# POWER.net
KiCad netlist of a schematic drawn in Altium Designer
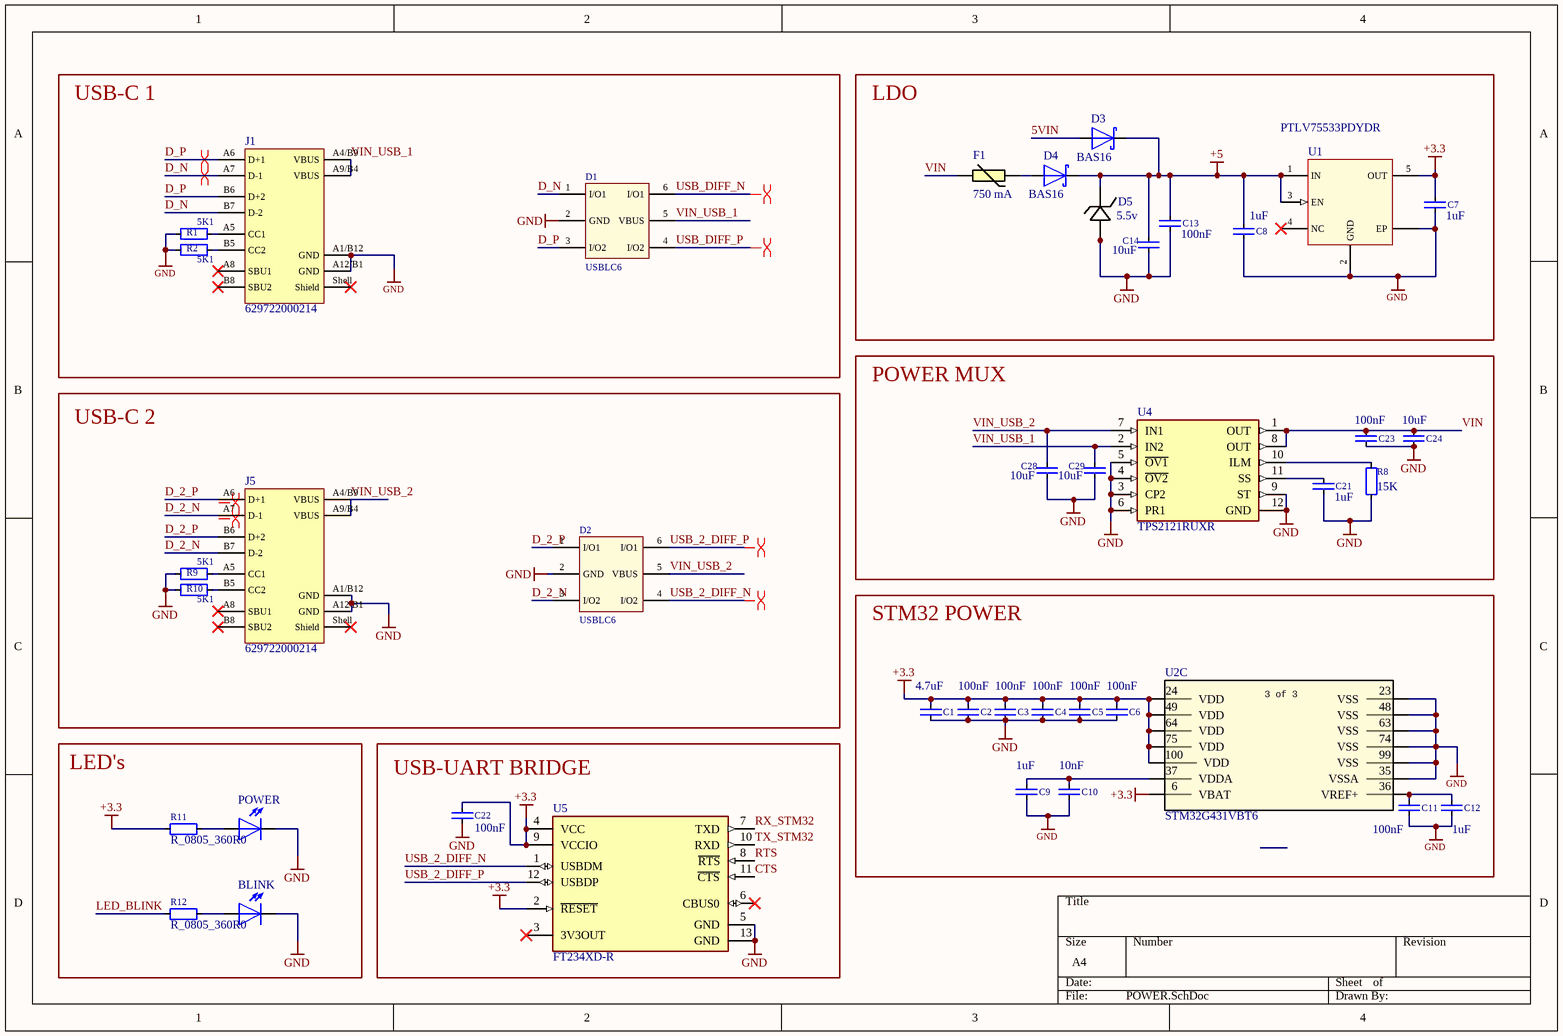
[diagram p0: POWER.SchDoc]

(export (version "E")
  (design (tool "Eeschema 10.0.6"))
  (components
    (comp (ref "BLINK")
      (value "LED_1206_GREEN")
      (footprint "WL-SMRW_1205_normal use")
      (description "LED, SMD, 1206, green")
      (fields
        (field (name "MANUFACTURER") "Würth Elektronik")
        (field (name "MANUFACTURER PART NUMBER") "156120GS75000")
      )
      (libsource (lib "CPNE-TI Electronic") (part "LED"))
    )
    (comp (ref "C1")
      (value "C_1206_4u70_X7R_25V")
      (footprint "SMD_1026_footprint")
      (fields
        (field (name "MANUFACTURER PART NUMBER") "12063C475KAT4A")
        (field (name "MANUFACTURER") "AVX Kyocera")
        (field (name "DISPLAYED VALUE") "4.7uF")
      )
      (libsource (lib "CPNE-TI Electronic") (part "Capacitor_Non-Polarized"))
    )
    (comp (ref "C2")
      (value "C_0805_100n0_X7R")
      (footprint "SMD_0805_footprint")
      (fields
        (field (name "MANUFACTURER PART NUMBER") "885012207098")
        (field (name "MANUFACTURER") "Würth Elektronik")
        (field (name "DISPLAYED VALUE") "100nF")
      )
      (libsource (lib "CPNE-TI Electronic") (part "Capacitor_Non-Polarized"))
    )
    (comp (ref "C3")
      (value "C_0805_100n0_X7R")
      (footprint "SMD_0805_footprint")
      (fields
        (field (name "MANUFACTURER PART NUMBER") "885012207098")
        (field (name "MANUFACTURER") "Würth Elektronik")
        (field (name "DISPLAYED VALUE") "100nF")
      )
      (libsource (lib "CPNE-TI Electronic") (part "Capacitor_Non-Polarized"))
    )
    (comp (ref "C4")
      (value "C_0805_100n0_X7R")
      (footprint "SMD_0805_footprint")
      (fields
        (field (name "MANUFACTURER PART NUMBER") "885012207098")
        (field (name "MANUFACTURER") "Würth Elektronik")
        (field (name "DISPLAYED VALUE") "100nF")
      )
      (libsource (lib "CPNE-TI Electronic") (part "Capacitor_Non-Polarized"))
    )
    (comp (ref "C5")
      (value "C_0805_100n0_X7R")
      (footprint "SMD_0805_footprint")
      (fields
        (field (name "MANUFACTURER PART NUMBER") "885012207098")
        (field (name "MANUFACTURER") "Würth Elektronik")
        (field (name "DISPLAYED VALUE") "100nF")
      )
      (libsource (lib "CPNE-TI Electronic") (part "Capacitor_Non-Polarized"))
    )
    (comp (ref "C6")
      (value "C_0805_100n0_X7R")
      (footprint "SMD_0805_footprint")
      (fields
        (field (name "MANUFACTURER PART NUMBER") "885012207098")
        (field (name "MANUFACTURER") "Würth Elektronik")
        (field (name "DISPLAYED VALUE") "100nF")
      )
      (libsource (lib "CPNE-TI Electronic") (part "Capacitor_Non-Polarized"))
    )
    (comp (ref "C7")
      (value "C_0805_1u00_X7R_16V")
      (footprint "SMD_0805_footprint")
      (description "Ceramic Capacitor 1uF 16V 10% X7R SMD 0805")
      (fields
        (field (name "MANUFACTURER") "multicomp Pro")
        (field (name "DISPLAYED VALUE") "1uF")
        (field (name "MANUFACTURER PART NUMBER") "MC0805B105K160CT")
      )
      (libsource (lib "CPNE-TI Electronic") (part "Capacitor_Non-Polarized"))
    )
    (comp (ref "C8")
      (value "C_0805_1u00_X7R_16V")
      (footprint "SMD_0805_footprint")
      (description "Ceramic Capacitor 1uF 16V 10% X7R SMD 0805")
      (fields
        (field (name "MANUFACTURER") "multicomp Pro")
        (field (name "DISPLAYED VALUE") "1uF")
        (field (name "MANUFACTURER PART NUMBER") "MC0805B105K160CT")
      )
      (libsource (lib "CPNE-TI Electronic") (part "Capacitor_Non-Polarized"))
    )
    (comp (ref "C9")
      (value "C_0805_1u00_X7R_16V")
      (footprint "SMD_0805_footprint")
      (description "Ceramic Capacitor 1uF 16V 10% X7R SMD 0805")
      (fields
        (field (name "MANUFACTURER") "multicomp Pro")
        (field (name "DISPLAYED VALUE") "1uF")
        (field (name "MANUFACTURER PART NUMBER") "MC0805B105K160CT")
      )
      (libsource (lib "CPNE-TI Electronic") (part "Capacitor_Non-Polarized"))
    )
    (comp (ref "C10")
      (value "C_0805_10n00_X7R_50V")
      (footprint "SMD_0805_footprint")
      (description "Multilayer Ceramic Capacitor 0.01uF 0805")
      (fields
        (field (name "MANUFACTURER") "Würth Elektronik")
        (field (name "DISPLAYED VALUE") "10nF")
        (field (name "MANUFACTURER PART NUMBER") "8850 1220 7092")
      )
      (libsource (lib "CPNE-TI Electronic") (part "Capacitor_Non-Polarized"))
    )
    (comp (ref "C11")
      (value "C_0805_100n0_X7R")
      (footprint "SMD_0805_footprint")
      (fields
        (field (name "MANUFACTURER PART NUMBER") "885012207098")
        (field (name "MANUFACTURER") "Würth Elektronik")
        (field (name "DISPLAYED VALUE") "100nF")
      )
      (libsource (lib "CPNE-TI Electronic") (part "Capacitor_Non-Polarized"))
    )
    (comp (ref "C12")
      (value "C_0805_1u00_X7R_16V")
      (footprint "SMD_0805_footprint")
      (description "Ceramic Capacitor 1uF 16V 10% X7R SMD 0805")
      (fields
        (field (name "MANUFACTURER") "multicomp Pro")
        (field (name "DISPLAYED VALUE") "1uF")
        (field (name "MANUFACTURER PART NUMBER") "MC0805B105K160CT")
      )
      (libsource (lib "CPNE-TI Electronic") (part "Capacitor_Non-Polarized"))
    )
    (comp (ref "C13")
      (value "C_0805_100n0_X7R")
      (footprint "SMD_0805_footprint")
      (fields
        (field (name "MANUFACTURER PART NUMBER") "885012207098")
        (field (name "MANUFACTURER") "Würth Elektronik")
        (field (name "DISPLAYED VALUE") "100nF")
      )
      (libsource (lib "CPNE-TI Electronic") (part "Capacitor_Non-Polarized"))
    )
    (comp (ref "C14")
      (value "C_1206_10u0_X7R_25V")
      (footprint "SMD_1026_footprint")
      (description "10μF ±10% 25V Ceramic Capacitor X7R 1206 (3216 Metric)")
      (fields
        (field (name "MANUFACTURER PART NUMBER") "885012208069")
        (field (name "DISPLAYED VALUE") "10uF")
        (field (name "MANUFACTURER") "Würth Elektronik")
      )
      (libsource (lib "CPNE-TI Electronic") (part "Capacitor_Non-Polarized"))
    )
    (comp (ref "C21")
      (value "C_0805_1u00_X7R_16V")
      (footprint "SMD_0805_footprint")
      (description "Ceramic Capacitor 1uF 16V 10% X7R SMD 0805")
      (fields
        (field (name "MANUFACTURER") "multicomp Pro")
        (field (name "DISPLAYED VALUE") "1uF")
        (field (name "MANUFACTURER PART NUMBER") "MC0805B105K160CT")
      )
      (libsource (lib "CPNE-TI Electronic") (part "Capacitor_Non-Polarized"))
    )
    (comp (ref "C22")
      (value "C_0805_100n0_X7R")
      (footprint "SMD_0805_footprint")
      (fields
        (field (name "MANUFACTURER PART NUMBER") "885012207098")
        (field (name "MANUFACTURER") "Würth Elektronik")
        (field (name "DISPLAYED VALUE") "100nF")
      )
      (libsource (lib "CPNE-TI Electronic") (part "Capacitor_Non-Polarized"))
    )
    (comp (ref "C23")
      (value "C_0805_100n0_X7R")
      (footprint "SMD_0805_footprint")
      (fields
        (field (name "MANUFACTURER PART NUMBER") "885012207098")
        (field (name "MANUFACTURER") "Würth Elektronik")
        (field (name "DISPLAYED VALUE") "100nF")
      )
      (libsource (lib "CPNE-TI Electronic") (part "Capacitor_Non-Polarized"))
    )
    (comp (ref "C24")
      (value "C_1206_10u0_X7R_25V")
      (footprint "SMD_1026_footprint")
      (description "10μF ±10% 25V Ceramic Capacitor X7R 1206 (3216 Metric)")
      (fields
        (field (name "MANUFACTURER PART NUMBER") "885012208069")
        (field (name "DISPLAYED VALUE") "10uF")
        (field (name "MANUFACTURER") "Würth Elektronik")
      )
      (libsource (lib "CPNE-TI Electronic") (part "Capacitor_Non-Polarized"))
    )
    (comp (ref "C28")
      (value "C_1206_10u0_X7R_25V")
      (footprint "SMD_1026_footprint")
      (description "10μF ±10% 25V Ceramic Capacitor X7R 1206 (3216 Metric)")
      (fields
        (field (name "MANUFACTURER PART NUMBER") "885012208069")
        (field (name "DISPLAYED VALUE") "10uF")
        (field (name "MANUFACTURER") "Würth Elektronik")
      )
      (libsource (lib "CPNE-TI Electronic") (part "Capacitor_Non-Polarized"))
    )
    (comp (ref "C29")
      (value "C_1206_10u0_X7R_25V")
      (footprint "SMD_1026_footprint")
      (description "10μF ±10% 25V Ceramic Capacitor X7R 1206 (3216 Metric)")
      (fields
        (field (name "MANUFACTURER PART NUMBER") "885012208069")
        (field (name "DISPLAYED VALUE") "10uF")
        (field (name "MANUFACTURER") "Würth Elektronik")
      )
      (libsource (lib "CPNE-TI Electronic") (part "Capacitor_Non-Polarized"))
    )
    (comp (ref "D1")
      (value "USBLC6-2SC6")
      (footprint "SOT23-6L_V")
      (description "5A 17V 6V Unidirectional 5.25V SOT-23-6L ESD and Surge Protection (TVS/ESD) ROHS")
      (fields (field (name "DISPLAYED VALUE") "USBLC6") (field (name "MANUFACTURER") "ST Microelectronics"))
      (libsource (lib "CPNE-TI Electronic") (part "USBLC6-2SC6-Symbol-1"))
    )
    (comp (ref "D2")
      (value "USBLC6-2SC6")
      (footprint "SOT23-6L_V")
      (description "5A 17V 6V Unidirectional 5.25V SOT-23-6L ESD and Surge Protection (TVS/ESD) ROHS")
      (fields (field (name "DISPLAYED VALUE") "USBLC6") (field (name "MANUFACTURER") "ST Microelectronics"))
      (libsource (lib "CPNE-TI Electronic") (part "USBLC6-2SC6-Symbol-1"))
    )
    (comp (ref "D3")
      (value "BAS16LT3G")
      (footprint "ONSC-SOT-23-3-318-08_V")
      (description "Rectifier Diode Small Signal Switching 0.2A 6ns 3-Pin SOT-23 T/R")
      (fields (field (name "DISPLAYED VALUE") "BAS16") (field (name "MANUFACTURER") "Onsemi"))
      (libsource (lib "CPNE-TI Electronic") (part "Schottky Diode SOT-23"))
    )
    (comp (ref "D4")
      (value "BAS16LT3G")
      (footprint "ONSC-SOT-23-3-318-08_V")
      (description "Rectifier Diode Small Signal Switching 0.2A 6ns 3-Pin SOT-23 T/R")
      (fields (field (name "DISPLAYED VALUE") "BAS16") (field (name "MANUFACTURER") "Onsemi"))
      (libsource (lib "CPNE-TI Electronic") (part "Schottky Diode SOT-23"))
    )
    (comp (ref "D5")
      (value "D5V0H1U2LP1610-7")
      (footprint "D5V0H1U2LP1610-7")
      (description "TVS Diode")
      (fields (field (name "DISPLAYED VALUE") "5.5v") (field (name "MANUFACTURER") "Diodes Incorporated"))
      (libsource (lib "CPNE-TI Electronic") (part "D5V0H1U2LP1610-7"))
    )
    (comp (ref "F1")
      (value "0ZCG0075FF2C")
      (footprint "0ZCG0075FF2C")
      (description "Polymérique PTC Resettable Fuse 16V 750 mA Ih Montage en surface 1812")
      (fields (field (name "MANUFACTURER") "Bel Fuse Inc.") (field (name "DISPLAYED VALUE") "750 mA"))
      (libsource (lib "CPNE-TI Electronic") (part "0ZCG0075FF2C"))
    )
    (comp (ref "J1")
      (value "629722000214")
      (footprint "629722000214")
      (description "Usb Conn, R/a, Type C 2.0, Rcpt, 16POS Rohs Compliant: Yes")
      (fields (field (name "MANUFACTURER") "Würth Elektronik"))
      (libsource (lib "CPNE-TI Electronic") (part "USB 2.0_Type C_Receptacle_1 Port_629722000214"))
    )
    (comp (ref "J5")
      (value "629722000214")
      (footprint "629722000214")
      (description "Usb Conn, R/a, Type C 2.0, Rcpt, 16POS Rohs Compliant: Yes")
      (fields (field (name "MANUFACTURER") "Würth Elektronik"))
      (libsource (lib "CPNE-TI Electronic") (part "USB 2.0_Type C_Receptacle_1 Port_629722000214"))
    )
    (comp (ref "POWER")
      (value "LED_1206_GREEN")
      (footprint "WL-SMRW_1205_normal use")
      (description "LED, SMD, 1206, green")
      (fields
        (field (name "MANUFACTURER") "Würth Elektronik")
        (field (name "MANUFACTURER PART NUMBER") "156120GS75000")
      )
      (libsource (lib "CPNE-TI Electronic") (part "LED"))
    )
    (comp (ref "R1")
      (value "R_0805_5K10")
      (footprint "SMD_0805_footprint")
      (description "Res Thick Film 0805 5.1K Ohm 1% 1/8W ±100ppm/°C Molded SMD Punched Carrier T/R")
      (fields
        (field (name "DISPLAYED VALUE") "5K1")
        (field (name "MANUFACTURER PART NUMBER") "ERJ-6ENF5101V")
        (field (name "MANUFACTURER") "Panasonic")
      )
      (libsource (lib "CPNE-TI Electronic") (part "Resistor_Symbol"))
    )
    (comp (ref "R2")
      (value "R_0805_5K10")
      (footprint "SMD_0805_footprint")
      (description "Res Thick Film 0805 5.1K Ohm 1% 1/8W ±100ppm/°C Molded SMD Punched Carrier T/R")
      (fields
        (field (name "DISPLAYED VALUE") "5K1")
        (field (name "MANUFACTURER PART NUMBER") "ERJ-6ENF5101V")
        (field (name "MANUFACTURER") "Panasonic")
      )
      (libsource (lib "CPNE-TI Electronic") (part "Resistor_Symbol"))
    )
    (comp (ref "R8")
      (value "R_0805_15K_0.125W")
      (footprint "SMD_0805_footprint")
      (description "Res Thick Film 0805 1.5K Ohm 1% 0.125W(1/8W) +/-100ppm/C Molded SMD Automotive Punched T/R")
      (fields
        (field (name "MANUFACTURER PART NUMBER") "ERJ-6ENF1501V")
        (field (name "DISPLAYED VALUE") "15K")
        (field (name "MANUFACTURER") "Panasonic")
      )
      (libsource (lib "") (part "Resistor_Symbol_1"))
    )
    (comp (ref "R9")
      (value "R_0805_5K10")
      (footprint "SMD_0805_footprint")
      (description "Res Thick Film 0805 5.1K Ohm 1% 1/8W ±100ppm/°C Molded SMD Punched Carrier T/R")
      (fields
        (field (name "DISPLAYED VALUE") "5K1")
        (field (name "MANUFACTURER PART NUMBER") "ERJ-6ENF5101V")
        (field (name "MANUFACTURER") "Panasonic")
      )
      (libsource (lib "CPNE-TI Electronic") (part "Resistor_Symbol"))
    )
    (comp (ref "R10")
      (value "R_0805_5K10")
      (footprint "SMD_0805_footprint")
      (description "Res Thick Film 0805 5.1K Ohm 1% 1/8W ±100ppm/°C Molded SMD Punched Carrier T/R")
      (fields
        (field (name "DISPLAYED VALUE") "5K1")
        (field (name "MANUFACTURER PART NUMBER") "ERJ-6ENF5101V")
        (field (name "MANUFACTURER") "Panasonic")
      )
      (libsource (lib "CPNE-TI Electronic") (part "Resistor_Symbol"))
    )
    (comp (ref "R11")
      (value "R_0805_360R0")
      (footprint "SMD_0805_footprint")
      (description "Res Thick Film 0805 360 Ohm 1% 0.125W ±100ppm/°C Molded SMD Punched Carrier T/R")
      (fields
        (field (name "MANUFACTURER PART NUMBER") "ERJ-6ENF3600V")
        (field (name "MANUFACTURER") "Panasonic")
      )
      (libsource (lib "CPNE-TI Electronic") (part "Resistor_Symbol"))
    )
    (comp (ref "R12")
      (value "R_0805_360R0")
      (footprint "SMD_0805_footprint")
      (description "Res Thick Film 0805 360 Ohm 1% 0.125W ±100ppm/°C Molded SMD Punched Carrier T/R")
      (fields
        (field (name "MANUFACTURER PART NUMBER") "ERJ-6ENF3600V")
        (field (name "MANUFACTURER") "Panasonic")
      )
      (libsource (lib "CPNE-TI Electronic") (part "Resistor_Symbol"))
    )
    (comp (ref "U1")
      (value "PTLV75533PDYDR")
      (footprint "DYD0005A-MFG")
      (description "500-mA high-PSRR low-IQ low-dropout voltage regulator with enable 5-SOT-23 -40 to 125")
      (fields (field (name "MANUFACTURER") "Texas Instruments"))
      (libsource (lib "CPNE-TI Electronic") (part "PTLV75533PDYDR"))
    )
    (comp (ref "U2")
      (value "STM32G431VBT6")
      (footprint "LQFP100")
      (description "Microcontroller 32-Bit ARM Cortex-M4 RISC 128KB Flash 1.71V to 3.6V 100-Pin LQFP")
      (libsource (lib "CPNE-TI Electronic") (part "STM32G431VBT6"))
    )
    (comp (ref "U4")
      (value "TPS2121RUXR")
      (footprint "FP-RUX0012A-MFG")
      (description "2.7-V to 22-V, 56-mΩ, 4.5-A, power mux with seamless switchover 12-VQFN-HR -40 to 125")
      (libsource (lib "CPNE-TI Electronic") (part "7e2eec2e55e3eba557c36dfb5d176d9"))
    )
    (comp (ref "U5")
      (value "FT234XD-R")
      (footprint "FP-DFN-12-MFG")
      (description "Tape & Reel (TR) 2006 UART USB 2.0 interface controller 2.97V~5.5V 800mum 8mA 3Mbps")
      (libsource (lib "CPNE-TI Electronic") (part "4bef3367ed9f9051bcb84ab46edda1c"))
    )
  )
  (nets
    (net (code "1") (name "+3.3") (class "Default")
      (node (ref "C1") (pin "2") (pinfunction "2_2") (pintype "passive"))
      (node (ref "C2") (pin "2") (pinfunction "2_2") (pintype "passive"))
      (node (ref "C22") (pin "1") (pinfunction "1_1") (pintype "passive"))
      (node (ref "C3") (pin "2") (pinfunction "2_2") (pintype "passive"))
      (node (ref "C4") (pin "2") (pinfunction "2_2") (pintype "passive"))
      (node (ref "C5") (pin "2") (pinfunction "2_2") (pintype "passive"))
      (node (ref "C6") (pin "2") (pinfunction "2_2") (pintype "passive"))
      (node (ref "C7") (pin "2") (pinfunction "2_2") (pintype "passive"))
      (node (ref "R11") (pin "1") (pinfunction "1_1") (pintype "passive"))
      (node (ref "U1") (pin "5") (pinfunction "OUT_5") (pintype "passive"))
      (node (ref "U2") (pin "100") (pinfunction "VDD_100") (pintype "power_in"))
      (node (ref "U2") (pin "24") (pinfunction "VDD_24") (pintype "power_in"))
      (node (ref "U2") (pin "49") (pinfunction "VDD_49") (pintype "power_in"))
      (node (ref "U2") (pin "6") (pinfunction "VBAT_6") (pintype "power_in"))
      (node (ref "U2") (pin "64") (pinfunction "VDD_64") (pintype "power_in"))
      (node (ref "U2") (pin "75") (pinfunction "VDD_75") (pintype "power_in"))
      (node (ref "U5") (pin "2") (pinfunction "~{RESET}_2") (pintype "input"))
      (node (ref "U5") (pin "4") (pinfunction "VCC_4") (pintype "power_in"))
      (node (ref "U5") (pin "9") (pinfunction "VCCIO_9") (pintype "power_in"))
    )
    (net (code "2") (name "+5") (class "Default")
      (node (ref "C13") (pin "2") (pinfunction "2_2") (pintype "passive"))
      (node (ref "C14") (pin "2") (pinfunction "2_2") (pintype "passive"))
      (node (ref "C8") (pin "2") (pinfunction "2_2") (pintype "passive"))
      (node (ref "D3") (pin "3") (pinfunction "K_3") (pintype "passive"))
      (node (ref "D4") (pin "3") (pinfunction "K_3") (pintype "passive"))
      (node (ref "D5") (pin "1") (pinfunction "1_1") (pintype "passive"))
      (node (ref "U1") (pin "1") (pinfunction "IN_1") (pintype "power_in"))
      (node (ref "U1") (pin "3") (pinfunction "EN_3") (pintype "input"))
    )
    (net (code "3") (name "/5VIN") (class "Default")
      (node (ref "D3") (pin "1") (pinfunction "A_1") (pintype "passive"))
    )
    (net (code "4") (name "/CTS") (class "Default")
      (node (ref "U5") (pin "11") (pinfunction "~{CTS}_11") (pintype "input"))
    )
    (net (code "5") (name "/D_2_N") (class "Default")
      (node (ref "D2") (pin "3") (pinfunction "I/O2_3") (pintype "passive"))
      (node (ref "J5") (pin "A7") (pinfunction "D-1_A7") (pintype "passive"))
      (node (ref "J5") (pin "B7") (pinfunction "D-2_B7") (pintype "passive"))
    )
    (net (code "6") (name "/D_2_P") (class "Default")
      (node (ref "D2") (pin "1") (pinfunction "I/O1_1") (pintype "passive"))
      (node (ref "J5") (pin "A6") (pinfunction "D+1_A6") (pintype "passive"))
      (node (ref "J5") (pin "B6") (pinfunction "D+2_B6") (pintype "passive"))
    )
    (net (code "7") (name "/D_N") (class "Default")
      (node (ref "D1") (pin "1") (pinfunction "I/O1_1") (pintype "passive"))
      (node (ref "J1") (pin "A7") (pinfunction "D-1_A7") (pintype "passive"))
      (node (ref "J1") (pin "B7") (pinfunction "D-2_B7") (pintype "passive"))
    )
    (net (code "8") (name "/D_P") (class "Default")
      (node (ref "D1") (pin "3") (pinfunction "I/O2_3") (pintype "passive"))
      (node (ref "J1") (pin "A6") (pinfunction "D+1_A6") (pintype "passive"))
      (node (ref "J1") (pin "B6") (pinfunction "D+2_B6") (pintype "passive"))
    )
    (net (code "9") (name "/LED_BLINK") (class "Default")
      (node (ref "R12") (pin "1") (pinfunction "1_1") (pintype "passive"))
    )
    (net (code "10") (name "/RTS") (class "Default")
      (node (ref "U5") (pin "8") (pinfunction "~{RTS}_8") (pintype "input"))
    )
    (net (code "11") (name "/RX_STM32") (class "Default")
      (node (ref "U5") (pin "7") (pinfunction "TXD_7") (pintype "output"))
    )
    (net (code "12") (name "/TX_STM32") (class "Default")
      (node (ref "U5") (pin "10") (pinfunction "RXD_10") (pintype "output"))
    )
    (net (code "13") (name "/USB_2_DIFF_N") (class "Default")
      (node (ref "D2") (pin "4") (pinfunction "I/O2_4") (pintype "passive"))
      (node (ref "U5") (pin "1") (pinfunction "USBDM_1") (pintype "bidirectional"))
    )
    (net (code "14") (name "/USB_2_DIFF_P") (class "Default")
      (node (ref "D2") (pin "6") (pinfunction "I/O1_6") (pintype "passive"))
      (node (ref "U5") (pin "12") (pinfunction "USBDP_12") (pintype "bidirectional"))
    )
    (net (code "15") (name "/USB_DIFF_N") (class "Default")
      (node (ref "D1") (pin "6") (pinfunction "I/O1_6") (pintype "passive"))
    )
    (net (code "16") (name "/USB_DIFF_P") (class "Default")
      (node (ref "D1") (pin "4") (pinfunction "I/O2_4") (pintype "passive"))
    )
    (net (code "17") (name "/VIN") (class "Default")
      (node (ref "C23") (pin "2") (pinfunction "2_2") (pintype "passive"))
      (node (ref "C24") (pin "2") (pinfunction "2_2") (pintype "passive"))
      (node (ref "F1") (pin "2") (pinfunction "2_2") (pintype "passive"))
      (node (ref "U4") (pin "1") (pinfunction "OUT_1") (pintype "output"))
      (node (ref "U4") (pin "8") (pinfunction "OUT_8") (pintype "output"))
    )
    (net (code "18") (name "/VIN_USB_1") (class "Default")
      (node (ref "C29") (pin "2") (pinfunction "2_2") (pintype "passive"))
      (node (ref "D1") (pin "5") (pinfunction "VBUS_5") (pintype "power_in"))
      (node (ref "J1") (pin "A4/B9") (pinfunction "VBUS_A4/B9") (pintype "passive"))
      (node (ref "J1") (pin "A9/B4") (pinfunction "VBUS_A9/B4") (pintype "passive"))
      (node (ref "U4") (pin "2") (pinfunction "IN2_2") (pintype "input"))
    )
    (net (code "19") (name "/VIN_USB_2") (class "Default")
      (node (ref "C28") (pin "2") (pinfunction "2_2") (pintype "passive"))
      (node (ref "D2") (pin "5") (pinfunction "VBUS_5") (pintype "power_in"))
      (node (ref "J5") (pin "A4/B9") (pinfunction "VBUS_A4/B9") (pintype "passive"))
      (node (ref "J5") (pin "A9/B4") (pinfunction "VBUS_A9/B4") (pintype "passive"))
      (node (ref "U4") (pin "7") (pinfunction "IN1_7") (pintype "input"))
    )
    (net (code "20") (name "GND") (class "Default")
      (node (ref "BLINK") (pin "1") (pinfunction "K_1") (pintype "passive"))
      (node (ref "C1") (pin "1") (pinfunction "1_1") (pintype "passive"))
      (node (ref "C10") (pin "1") (pinfunction "1_1") (pintype "passive"))
      (node (ref "C11") (pin "1") (pinfunction "1_1") (pintype "passive"))
      (node (ref "C12") (pin "1") (pinfunction "1_1") (pintype "passive"))
      (node (ref "C13") (pin "1") (pinfunction "1_1") (pintype "passive"))
      (node (ref "C14") (pin "1") (pinfunction "1_1") (pintype "passive"))
      (node (ref "C2") (pin "1") (pinfunction "1_1") (pintype "passive"))
      (node (ref "C21") (pin "1") (pinfunction "1_1") (pintype "passive"))
      (node (ref "C22") (pin "2") (pinfunction "2_2") (pintype "passive"))
      (node (ref "C23") (pin "1") (pinfunction "1_1") (pintype "passive"))
      (node (ref "C24") (pin "1") (pinfunction "1_1") (pintype "passive"))
      (node (ref "C28") (pin "1") (pinfunction "1_1") (pintype "passive"))
      (node (ref "C29") (pin "1") (pinfunction "1_1") (pintype "passive"))
      (node (ref "C3") (pin "1") (pinfunction "1_1") (pintype "passive"))
      (node (ref "C4") (pin "1") (pinfunction "1_1") (pintype "passive"))
      (node (ref "C5") (pin "1") (pinfunction "1_1") (pintype "passive"))
      (node (ref "C6") (pin "1") (pinfunction "1_1") (pintype "passive"))
      (node (ref "C7") (pin "1") (pinfunction "1_1") (pintype "passive"))
      (node (ref "C8") (pin "1") (pinfunction "1_1") (pintype "passive"))
      (node (ref "C9") (pin "1") (pinfunction "1_1") (pintype "passive"))
      (node (ref "D1") (pin "2") (pinfunction "GND_2") (pintype "power_in"))
      (node (ref "D2") (pin "2") (pinfunction "GND_2") (pintype "power_in"))
      (node (ref "D5") (pin "2") (pinfunction "2_2") (pintype "passive"))
      (node (ref "J1") (pin "A1/B12") (pinfunction "GND_A1/B12") (pintype "passive"))
      (node (ref "J1") (pin "A12/B1") (pinfunction "GND_A12/B1") (pintype "passive"))
      (node (ref "J5") (pin "A1/B12") (pinfunction "GND_A1/B12") (pintype "passive"))
      (node (ref "J5") (pin "A12/B1") (pinfunction "GND_A12/B1") (pintype "passive"))
      (node (ref "POWER") (pin "1") (pinfunction "K_1") (pintype "passive"))
      (node (ref "R1") (pin "1") (pinfunction "1_1") (pintype "passive"))
      (node (ref "R10") (pin "1") (pinfunction "1_1") (pintype "passive"))
      (node (ref "R2") (pin "1") (pinfunction "1_1") (pintype "passive"))
      (node (ref "R8") (pin "1") (pinfunction "1_1") (pintype "passive"))
      (node (ref "R9") (pin "1") (pinfunction "1_1") (pintype "passive"))
      (node (ref "U1") (pin "2") (pinfunction "GND_2") (pintype "power_in"))
      (node (ref "U1") (pin "EP") (pinfunction "EP_EP") (pintype "power_in"))
      (node (ref "U2") (pin "23") (pinfunction "VSS_23") (pintype "power_in"))
      (node (ref "U2") (pin "35") (pinfunction "VSSA_35") (pintype "power_in"))
      (node (ref "U2") (pin "48") (pinfunction "VSS_48") (pintype "power_in"))
      (node (ref "U2") (pin "63") (pinfunction "VSS_63") (pintype "power_in"))
      (node (ref "U2") (pin "74") (pinfunction "VSS_74") (pintype "power_in"))
      (node (ref "U2") (pin "99") (pinfunction "VSS_99") (pintype "power_in"))
      (node (ref "U4") (pin "12") (pinfunction "GND_12") (pintype "power_in"))
      (node (ref "U4") (pin "3") (pinfunction "CP2_3") (pintype "input"))
      (node (ref "U4") (pin "4") (pinfunction "~{OV2}_4") (pintype "input"))
      (node (ref "U4") (pin "5") (pinfunction "~{OV1}_5") (pintype "input"))
      (node (ref "U4") (pin "6") (pinfunction "PR1_6") (pintype "input"))
      (node (ref "U4") (pin "9") (pinfunction "ST_9") (pintype "output"))
      (node (ref "U5") (pin "13") (pinfunction "GND_13") (pintype "power_in"))
      (node (ref "U5") (pin "5") (pinfunction "GND_5") (pintype "power_in"))
    )
    (net (code "21") (name "Net-(BLINK-A)") (class "Default")
      (node (ref "BLINK") (pin "2") (pinfunction "A_2") (pintype "passive"))
      (node (ref "R12") (pin "2") (pinfunction "2_2") (pintype "passive"))
    )
    (net (code "22") (name "Net-(D4-A)") (class "Default")
      (node (ref "D4") (pin "1") (pinfunction "A_1") (pintype "passive"))
      (node (ref "F1") (pin "1") (pinfunction "1_1") (pintype "passive"))
    )
    (net (code "23") (name "Net-(J1-CC1)") (class "Default")
      (node (ref "J1") (pin "A5") (pinfunction "CC1_A5") (pintype "passive"))
      (node (ref "R1") (pin "2") (pinfunction "2_2") (pintype "passive"))
    )
    (net (code "24") (name "Net-(J1-CC2)") (class "Default")
      (node (ref "J1") (pin "B5") (pinfunction "CC2_B5") (pintype "passive"))
      (node (ref "R2") (pin "2") (pinfunction "2_2") (pintype "passive"))
    )
    (net (code "25") (name "Net-(J5-CC1)") (class "Default")
      (node (ref "J5") (pin "A5") (pinfunction "CC1_A5") (pintype "passive"))
      (node (ref "R9") (pin "2") (pinfunction "2_2") (pintype "passive"))
    )
    (net (code "26") (name "Net-(J5-CC2)") (class "Default")
      (node (ref "J5") (pin "B5") (pinfunction "CC2_B5") (pintype "passive"))
      (node (ref "R10") (pin "2") (pinfunction "2_2") (pintype "passive"))
    )
    (net (code "27") (name "Net-(POWER-A)") (class "Default")
      (node (ref "POWER") (pin "2") (pinfunction "A_2") (pintype "passive"))
      (node (ref "R11") (pin "2") (pinfunction "2_2") (pintype "passive"))
    )
    (net (code "28") (name "Net-(U2C-VDDA)") (class "Default")
      (node (ref "C10") (pin "2") (pinfunction "2_2") (pintype "passive"))
      (node (ref "C9") (pin "2") (pinfunction "2_2") (pintype "passive"))
      (node (ref "U2") (pin "37") (pinfunction "VDDA_37") (pintype "power_in"))
    )
    (net (code "29") (name "Net-(U2C-VREF+)") (class "Default")
      (node (ref "C11") (pin "2") (pinfunction "2_2") (pintype "passive"))
      (node (ref "C12") (pin "2") (pinfunction "2_2") (pintype "passive"))
      (node (ref "U2") (pin "36") (pinfunction "VREF+_36") (pintype "power_in"))
    )
    (net (code "30") (name "Net-(U4-ILM)") (class "Default")
      (node (ref "R8") (pin "2") (pinfunction "2_2") (pintype "passive"))
      (node (ref "U4") (pin "10") (pinfunction "ILM_10") (pintype "output"))
    )
    (net (code "31") (name "Net-(U4-SS)") (class "Default")
      (node (ref "C21") (pin "2") (pinfunction "2_2") (pintype "passive"))
      (node (ref "U4") (pin "11") (pinfunction "SS_11") (pintype "output"))
    )
    (net (code "32") (name "unconnected-(J1-SBU1-PadA8)") (class "Default")
      (node (ref "J1") (pin "A8") (pinfunction "SBU1_A8") (pintype "passive+no_connect"))
    )
    (net (code "33") (name "unconnected-(J1-SBU2-PadB8)") (class "Default")
      (node (ref "J1") (pin "B8") (pinfunction "SBU2_B8") (pintype "passive+no_connect"))
    )
    (net (code "34") (name "unconnected-(J1-Shield-PadShell)") (class "Default")
      (node (ref "J1") (pin "Shell") (pinfunction "Shield_Shell") (pintype "passive+no_connect"))
    )
    (net (code "35") (name "unconnected-(J5-SBU1-PadA8)") (class "Default")
      (node (ref "J5") (pin "A8") (pinfunction "SBU1_A8") (pintype "passive+no_connect"))
    )
    (net (code "36") (name "unconnected-(J5-SBU2-PadB8)") (class "Default")
      (node (ref "J5") (pin "B8") (pinfunction "SBU2_B8") (pintype "passive+no_connect"))
    )
    (net (code "37") (name "unconnected-(J5-Shield-PadShell)") (class "Default")
      (node (ref "J5") (pin "Shell") (pinfunction "Shield_Shell") (pintype "passive+no_connect"))
    )
    (net (code "38") (name "unconnected-(U1-NC-Pad4)") (class "Default")
      (node (ref "U1") (pin "4") (pinfunction "NC_4") (pintype "passive+no_connect"))
    )
    (net (code "39") (name "unconnected-(U5-3V3OUT-Pad3)") (class "Default")
      (node (ref "U5") (pin "3") (pinfunction "3V3OUT_3") (pintype "power_in+no_connect"))
    )
    (net (code "40") (name "unconnected-(U5-CBUS0-Pad6)") (class "Default")
      (node (ref "U5") (pin "6") (pinfunction "CBUS0_6") (pintype "bidirectional+no_connect"))
    )
  )
)
